# meteo-slave.net
KiCad netlist of a schematic drawn in EAGLE
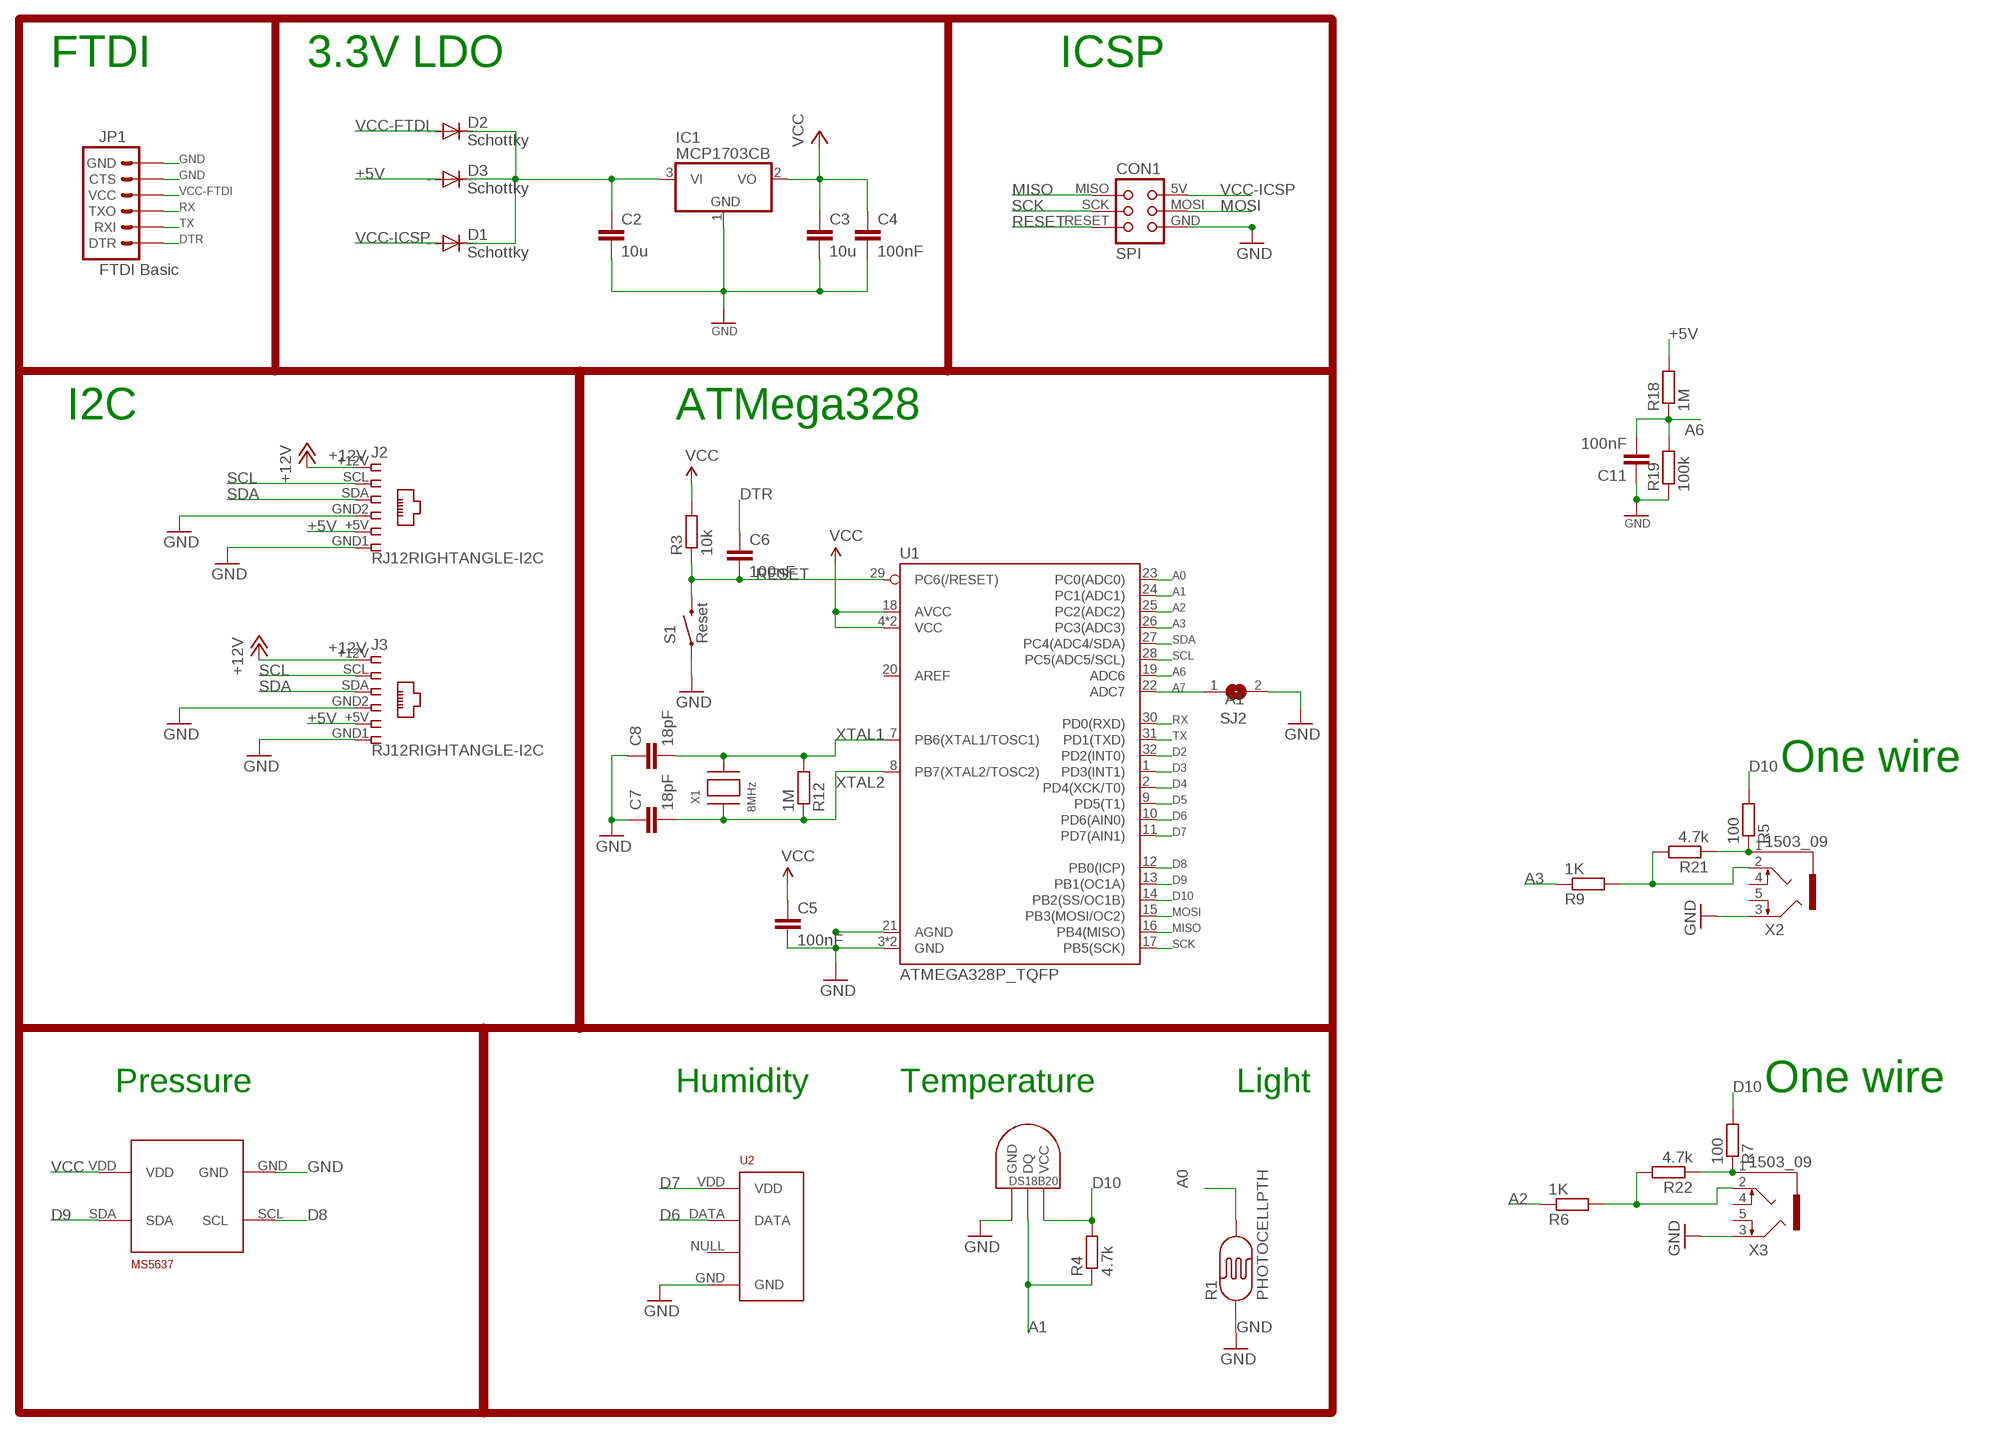
[diagram p0: schematic, sheet 1]

(export (version "E")
  (design (tool "Eeschema 10.0.6"))
  (components
    (comp (ref "C2")
      (value "10u")
      (footprint "eagle-import:C0805K")
      (fields (field (name "MPN") "77-VJ1206V106ZXQTBC"))
      (libsource (lib "eagle-import") (part "C-EUC0805K"))
    )
    (comp (ref "C3")
      (value "10u")
      (footprint "eagle-import:C0805K")
      (fields (field (name "MPN") "77-VJ1206V106ZXQTBC"))
      (libsource (lib "eagle-import") (part "C-EUC0805K"))
    )
    (comp (ref "C4")
      (value "100nF")
      (footprint "eagle-import:C0805K")
      (fields (field (name "MPN") "80-C1206C104K5R"))
      (libsource (lib "eagle-import") (part "C-EUC0805K"))
    )
    (comp (ref "C5")
      (value "100nF")
      (footprint "eagle-import:C0805K")
      (fields (field (name "MPN") "80-C1206C104K5R"))
      (libsource (lib "eagle-import") (part "C-EUC0805K"))
    )
    (comp (ref "C6")
      (value "100nF")
      (footprint "eagle-import:C0805K")
      (fields (field (name "MPN") "80-C1206C104K5R"))
      (libsource (lib "eagle-import") (part "C-EUC0805K"))
    )
    (comp (ref "C7")
      (value "18pF")
      (footprint "eagle-import:C0805K")
      (fields (field (name "MPN") "77-VJ1206A180JXXPBC"))
      (libsource (lib "eagle-import") (part "C-EUC0805K"))
    )
    (comp (ref "C8")
      (value "18pF")
      (footprint "eagle-import:C0805K")
      (fields (field (name "MPN") "77-VJ1206A180JXXPBC"))
      (libsource (lib "eagle-import") (part "C-EUC0805K"))
    )
    (comp (ref "C11")
      (value "100nF")
      (footprint "eagle-import:C0805K")
      (fields (field (name "MPN") "80-C1206C104K5R"))
      (libsource (lib "eagle-import") (part "C-EUC0805K"))
    )
    (comp (ref "CON1")
      (value "SPI")
      (footprint "eagle-import:TC2030-MCP")
      (libsource (lib "eagle-import") (part "TINYISPTAG"))
    )
    (comp (ref "D1")
      (value "Schottky")
      (footprint "eagle-import:SOD123")
      (fields (field (name "MPN") "621-1N5819HW-F"))
      (libsource (lib "eagle-import") (part "MBR0520LT"))
    )
    (comp (ref "D2")
      (value "Schottky")
      (footprint "eagle-import:SOD123")
      (fields (field (name "MPN") "621-1N5819HW-F"))
      (libsource (lib "eagle-import") (part "MBR0520LT"))
    )
    (comp (ref "D3")
      (value "Schottky")
      (footprint "eagle-import:SOD123")
      (fields (field (name "MPN") "621-1N5819HW-F"))
      (libsource (lib "eagle-import") (part "MBR0520LT"))
    )
    (comp (ref "IC1")
      (value "MCP1703CB")
      (footprint "eagle-import:SOT23")
      (libsource (lib "eagle-import") (part "MCP1703CB"))
    )
    (comp (ref "J2")
      (value "RJ12RIGHTANGLE-I2C")
      (footprint "eagle-import:RJ12-RIGHTANGLE-I2C")
      (libsource (lib "eagle-import") (part "RJ12RIGHTANGLE-I2C"))
    )
    (comp (ref "J3")
      (value "RJ12RIGHTANGLE-I2C")
      (footprint "eagle-import:RJ12-RIGHTANGLE-I2C")
      (libsource (lib "eagle-import") (part "RJ12RIGHTANGLE-I2C"))
    )
    (comp (ref "JP1")
      (value "FTDI Basic")
      (footprint "eagle-import:1X06")
      (libsource (lib "eagle-import") (part "ARDUINO_SERIAL_PROGRAMPTH"))
    )
    (comp (ref "R1")
      (value "PHOTOCELLPTH")
      (footprint "eagle-import:PHOTOCELL")
      (libsource (lib "eagle-import") (part "PHOTOCELLPTH"))
    )
    (comp (ref "R3")
      (value "10k")
      (footprint "eagle-import:R0805")
      (libsource (lib "eagle-import") (part "R-EU_R0805"))
    )
    (comp (ref "R4")
      (value "4.7k")
      (footprint "eagle-import:R0805")
      (libsource (lib "eagle-import") (part "resistor_348_R-EU_R0805"))
    )
    (comp (ref "R5")
      (value "100")
      (footprint "eagle-import:R0805")
      (libsource (lib "eagle-import") (part "R-EU_R0805"))
    )
    (comp (ref "R6")
      (value "1K")
      (footprint "eagle-import:R0805")
      (libsource (lib "eagle-import") (part "R-EU_R0805"))
    )
    (comp (ref "R7")
      (value "100")
      (footprint "eagle-import:R0805")
      (libsource (lib "eagle-import") (part "R-EU_R0805"))
    )
    (comp (ref "R9")
      (value "1K")
      (footprint "eagle-import:R0805")
      (libsource (lib "eagle-import") (part "R-EU_R0805"))
    )
    (comp (ref "R12")
      (value "1M")
      (footprint "eagle-import:R0805")
      (libsource (lib "eagle-import") (part "R-EU_R0805"))
    )
    (comp (ref "R18")
      (value "1M")
      (footprint "eagle-import:R0805")
      (libsource (lib "eagle-import") (part "R-EU_R0805"))
    )
    (comp (ref "R19")
      (value "100k")
      (footprint "eagle-import:R0805")
      (libsource (lib "eagle-import") (part "R-EU_R0805"))
    )
    (comp (ref "R21")
      (value "4.7k")
      (footprint "eagle-import:R0805")
      (libsource (lib "eagle-import") (part "resistor_R-EU_R0805"))
    )
    (comp (ref "R22")
      (value "4.7k")
      (footprint "eagle-import:R0805")
      (libsource (lib "eagle-import") (part "resistor_R-EU_R0805"))
    )
    (comp (ref "S1")
      (value "Reset")
      (footprint "eagle-import:TACTILE-SWITCH-SMD-ALT01")
      (libsource (lib "eagle-import") (part "SWITCH-MOMENTARY-2SMD-ALT01"))
    )
    (comp (ref "SJ2") (value "A1") (footprint "eagle-import:SJ") (libsource (lib "eagle-import") (part "SJ")))
    (comp (ref "U$1")
      (value "DS1820TO92")
      (footprint "eagle-import:DS1820")
      (libsource (lib "eagle-import") (part "DS1820TO92"))
    )
    (comp (ref "U$19")
      (value "MS5637WIDE")
      (footprint "eagle-import:MS5637WIDE")
      (libsource (lib "eagle-import") (part "MS5637WIDE"))
    )
    (comp (ref "U1")
      (value "ATMEGA328P_TQFP")
      (footprint "eagle-import:TQFP32-08")
      (libsource (lib "eagle-import") (part "ATMEGA328P_TQFP"))
    )
    (comp (ref "U2")
      (value "RHT03_DHT-22_AM2302")
      (footprint "eagle-import:RHT03_DHT-22")
      (libsource (lib "eagle-import") (part "RHT03_DHT-22_AM2302"))
    )
    (comp (ref "X1")
      (value "8MHz")
      (footprint "eagle-import:NX6035")
      (fields (field (name "MPN") "729-F60800010"))
      (libsource (lib "eagle-import") (part "XTALNX6035"))
    )
    (comp (ref "X2")
      (value "1503_09")
      (footprint "eagle-import:1503_09")
      (libsource (lib "eagle-import") (part "1503_09"))
    )
    (comp (ref "X3")
      (value "1503_09")
      (footprint "eagle-import:1503_09")
      (libsource (lib "eagle-import") (part "1503_09"))
    )
  )
  (nets
    (net (code "1") (name "+5V") (class "Default")
      (node (ref "D3") (pin "A") (pinfunction "A_A") (pintype "passive"))
      (node (ref "J2") (pin "+5V") (pinfunction "5_+5V") (pintype "bidirectional"))
      (node (ref "J3") (pin "+5V") (pinfunction "5_+5V") (pintype "bidirectional"))
      (node (ref "R18") (pin "2") (pinfunction "2_2") (pintype "passive"))
    )
    (net (code "2") (name "+12V") (class "Default")
      (node (ref "J2") (pin "+12V") (pinfunction "1_+12V") (pintype "bidirectional"))
      (node (ref "J3") (pin "+12V") (pinfunction "1_+12V") (pintype "bidirectional"))
    )
    (net (code "3") (name "A0") (class "Default")
      (node (ref "R1") (pin "2") (pinfunction "P$2_2") (pintype "bidirectional"))
      (node (ref "U1") (pin "23") (pinfunction "PC0(ADC0)_23") (pintype "bidirectional"))
    )
    (net (code "4") (name "A1") (class "Default")
      (node (ref "R4") (pin "1") (pinfunction "1_1") (pintype "passive"))
      (node (ref "U$1") (pin "DQ") (pinfunction "DQ_DQ") (pintype "bidirectional"))
      (node (ref "U1") (pin "24") (pinfunction "PC1(ADC1)_24") (pintype "bidirectional"))
    )
    (net (code "5") (name "A2") (class "Default")
      (node (ref "R6") (pin "1") (pinfunction "1_1") (pintype "passive"))
      (node (ref "U1") (pin "25") (pinfunction "PC2(ADC2)_25") (pintype "bidirectional"))
    )
    (net (code "6") (name "A3") (class "Default")
      (node (ref "R9") (pin "1") (pinfunction "1_1") (pintype "passive"))
      (node (ref "U1") (pin "26") (pinfunction "PC3(ADC3)_26") (pintype "bidirectional"))
    )
    (net (code "7") (name "A6") (class "Default")
      (node (ref "C11") (pin "2") (pinfunction "2_2") (pintype "passive"))
      (node (ref "R18") (pin "1") (pinfunction "1_1") (pintype "passive"))
      (node (ref "R19") (pin "2") (pinfunction "2_2") (pintype "passive"))
      (node (ref "U1") (pin "19") (pinfunction "ADC6_19") (pintype "bidirectional"))
    )
    (net (code "8") (name "A7") (class "Default")
      (node (ref "SJ2") (pin "1") (pinfunction "1_1") (pintype "passive"))
      (node (ref "U1") (pin "22") (pinfunction "ADC7_22") (pintype "bidirectional"))
    )
    (net (code "9") (name "D2") (class "Default")
      (node (ref "U1") (pin "32") (pinfunction "PD2(INT0)_32") (pintype "bidirectional"))
    )
    (net (code "10") (name "D3") (class "Default")
      (node (ref "U1") (pin "1") (pinfunction "PD3(INT1)_1") (pintype "bidirectional"))
    )
    (net (code "11") (name "D4") (class "Default")
      (node (ref "U1") (pin "2") (pinfunction "PD4(XCK/T0)_2") (pintype "bidirectional"))
    )
    (net (code "12") (name "D5") (class "Default")
      (node (ref "U1") (pin "9") (pinfunction "PD5(T1)_9") (pintype "bidirectional"))
    )
    (net (code "13") (name "D6") (class "Default")
      (node (ref "U1") (pin "10") (pinfunction "PD6(AIN0)_10") (pintype "bidirectional"))
      (node (ref "U2") (pin "DATA") (pinfunction "DATA_DATA") (pintype "bidirectional"))
    )
    (net (code "14") (name "D7") (class "Default")
      (node (ref "U1") (pin "11") (pinfunction "PD7(AIN1)_11") (pintype "bidirectional"))
      (node (ref "U2") (pin "VDD") (pinfunction "VDD_VDD") (pintype "power_in"))
    )
    (net (code "15") (name "D8") (class "Default")
      (node (ref "U$19") (pin "SCL") (pinfunction "SCL_SCL") (pintype "bidirectional"))
      (node (ref "U1") (pin "12") (pinfunction "PB0(ICP)_12") (pintype "bidirectional"))
    )
    (net (code "16") (name "D9") (class "Default")
      (node (ref "U$19") (pin "SDA") (pinfunction "SDA_SDA") (pintype "bidirectional"))
      (node (ref "U1") (pin "13") (pinfunction "PB1(OC1A)_13") (pintype "bidirectional"))
    )
    (net (code "17") (name "D10") (class "Default")
      (node (ref "R4") (pin "2") (pinfunction "2_2") (pintype "passive"))
      (node (ref "R5") (pin "2") (pinfunction "2_2") (pintype "passive"))
      (node (ref "R7") (pin "2") (pinfunction "2_2") (pintype "passive"))
      (node (ref "U$1") (pin "VDD") (pinfunction "VCC_VDD") (pintype "power_in"))
      (node (ref "U1") (pin "14") (pinfunction "PB2(SS/OC1B)_14") (pintype "bidirectional"))
    )
    (net (code "18") (name "DTR") (class "Default")
      (node (ref "C6") (pin "1") (pinfunction "1_1") (pintype "passive"))
      (node (ref "JP1") (pin "1") (pinfunction "DTR_1") (pintype "passive"))
    )
    (net (code "19") (name "GND") (class "Default")
      (node (ref "C11") (pin "1") (pinfunction "1_1") (pintype "passive"))
      (node (ref "C2") (pin "2") (pinfunction "2_2") (pintype "passive"))
      (node (ref "C3") (pin "2") (pinfunction "2_2") (pintype "passive"))
      (node (ref "C4") (pin "2") (pinfunction "2_2") (pintype "passive"))
      (node (ref "C5") (pin "2") (pinfunction "2_2") (pintype "passive"))
      (node (ref "C7") (pin "1") (pinfunction "1_1") (pintype "passive"))
      (node (ref "C8") (pin "1") (pinfunction "1_1") (pintype "passive"))
      (node (ref "CON1") (pin "GND") (pinfunction "GND_GND") (pintype "passive"))
      (node (ref "IC1") (pin "1") (pinfunction "GND_1") (pintype "passive"))
      (node (ref "J2") (pin "GND1") (pinfunction "6_GND1") (pintype "bidirectional"))
      (node (ref "J2") (pin "GND2") (pinfunction "4_GND2") (pintype "bidirectional"))
      (node (ref "J3") (pin "GND1") (pinfunction "6_GND1") (pintype "bidirectional"))
      (node (ref "J3") (pin "GND2") (pinfunction "4_GND2") (pintype "bidirectional"))
      (node (ref "JP1") (pin "5") (pinfunction "CTS_5") (pintype "passive"))
      (node (ref "JP1") (pin "6") (pinfunction "GND_6") (pintype "passive"))
      (node (ref "R1") (pin "1") (pinfunction "P$1_1") (pintype "bidirectional"))
      (node (ref "R19") (pin "1") (pinfunction "1_1") (pintype "passive"))
      (node (ref "S1") (pin "1") (pinfunction "1_1") (pintype "passive"))
      (node (ref "S1") (pin "2") (pinfunction "1_2") (pintype "passive"))
      (node (ref "SJ2") (pin "2") (pinfunction "2_2") (pintype "passive"))
      (node (ref "U$1") (pin "GND") (pinfunction "GND_GND") (pintype "power_in"))
      (node (ref "U$19") (pin "GND") (pinfunction "GND_GND") (pintype "bidirectional"))
      (node (ref "U1") (pin "21") (pinfunction "AGND_21") (pintype "bidirectional"))
      (node (ref "U1") (pin "3") (pinfunction "GND_3") (pintype "bidirectional"))
      (node (ref "U1") (pin "5") (pinfunction "GND_5") (pintype "bidirectional"))
      (node (ref "U2") (pin "GND") (pinfunction "GND_GND") (pintype "power_in"))
      (node (ref "X2") (pin "3") (pinfunction "3_3") (pintype "passive"))
      (node (ref "X3") (pin "3") (pinfunction "3_3") (pintype "passive"))
    )
    (net (code "20") (name "MISO") (class "Default")
      (node (ref "CON1") (pin "MISO") (pinfunction "MISO_MISO") (pintype "passive"))
      (node (ref "U1") (pin "16") (pinfunction "PB4(MISO)_16") (pintype "bidirectional"))
    )
    (net (code "21") (name "MOSI") (class "Default")
      (node (ref "CON1") (pin "MOSI") (pinfunction "MOSI_MOSI") (pintype "passive"))
      (node (ref "U1") (pin "15") (pinfunction "PB3(MOSI/OC2)_15") (pintype "bidirectional"))
    )
    (net (code "22") (name "Net-(IC1-VI)") (class "Default")
      (node (ref "C2") (pin "1") (pinfunction "1_1") (pintype "passive"))
      (node (ref "D1") (pin "C") (pinfunction "C_C") (pintype "passive"))
      (node (ref "D2") (pin "C") (pinfunction "C_C") (pintype "passive"))
      (node (ref "D3") (pin "C") (pinfunction "C_C") (pintype "passive"))
      (node (ref "IC1") (pin "3") (pinfunction "VI_3") (pintype "input"))
    )
    (net (code "23") (name "Net-(R21-Pad1)") (class "Default")
      (node (ref "R21") (pin "1") (pinfunction "1_1") (pintype "passive"))
      (node (ref "R5") (pin "1") (pinfunction "1_1") (pintype "passive"))
      (node (ref "X2") (pin "1") (pinfunction "1_1") (pintype "passive"))
    )
    (net (code "24") (name "Net-(R21-Pad2)") (class "Default")
      (node (ref "R21") (pin "2") (pinfunction "2_2") (pintype "passive"))
      (node (ref "R9") (pin "2") (pinfunction "2_2") (pintype "passive"))
      (node (ref "X2") (pin "2") (pinfunction "2_2") (pintype "passive"))
    )
    (net (code "25") (name "Net-(R22-Pad1)") (class "Default")
      (node (ref "R22") (pin "1") (pinfunction "1_1") (pintype "passive"))
      (node (ref "R7") (pin "1") (pinfunction "1_1") (pintype "passive"))
      (node (ref "X3") (pin "1") (pinfunction "1_1") (pintype "passive"))
    )
    (net (code "26") (name "Net-(R22-Pad2)") (class "Default")
      (node (ref "R22") (pin "2") (pinfunction "2_2") (pintype "passive"))
      (node (ref "R6") (pin "2") (pinfunction "2_2") (pintype "passive"))
      (node (ref "X3") (pin "2") (pinfunction "2_2") (pintype "passive"))
    )
    (net (code "27") (name "RESET") (class "Default")
      (node (ref "C6") (pin "2") (pinfunction "2_2") (pintype "passive"))
      (node (ref "CON1") (pin "RESET") (pinfunction "RESET_RESET") (pintype "passive"))
      (node (ref "R3") (pin "1") (pinfunction "1_1") (pintype "passive"))
      (node (ref "S1") (pin "3") (pinfunction "2_3") (pintype "passive"))
      (node (ref "S1") (pin "4") (pinfunction "2_4") (pintype "passive"))
      (node (ref "U1") (pin "29") (pinfunction "PC6(/RESET)_29") (pintype "bidirectional"))
    )
    (net (code "28") (name "RX") (class "Default")
      (node (ref "JP1") (pin "3") (pinfunction "TXO_3") (pintype "passive"))
      (node (ref "U1") (pin "30") (pinfunction "PD0(RXD)_30") (pintype "bidirectional"))
    )
    (net (code "29") (name "SCK") (class "Default")
      (node (ref "CON1") (pin "SCK") (pinfunction "SCK_SCK") (pintype "passive"))
      (node (ref "U1") (pin "17") (pinfunction "PB5(SCK)_17") (pintype "bidirectional"))
    )
    (net (code "30") (name "SCL") (class "Default")
      (node (ref "J2") (pin "SCL") (pinfunction "2_SCL") (pintype "bidirectional"))
      (node (ref "J3") (pin "SCL") (pinfunction "2_SCL") (pintype "bidirectional"))
      (node (ref "U1") (pin "28") (pinfunction "PC5(ADC5/SCL)_28") (pintype "bidirectional"))
    )
    (net (code "31") (name "SDA") (class "Default")
      (node (ref "J2") (pin "SDA") (pinfunction "3_SDA") (pintype "bidirectional"))
      (node (ref "J3") (pin "SDA") (pinfunction "3_SDA") (pintype "bidirectional"))
      (node (ref "U1") (pin "27") (pinfunction "PC4(ADC4/SDA)_27") (pintype "bidirectional"))
    )
    (net (code "32") (name "TX") (class "Default")
      (node (ref "JP1") (pin "2") (pinfunction "RXI_2") (pintype "passive"))
      (node (ref "U1") (pin "31") (pinfunction "PD1(TXD)_31") (pintype "bidirectional"))
    )
    (net (code "33") (name "VCC") (class "Default")
      (node (ref "C3") (pin "1") (pinfunction "1_1") (pintype "passive"))
      (node (ref "C4") (pin "1") (pinfunction "1_1") (pintype "passive"))
      (node (ref "C5") (pin "1") (pinfunction "1_1") (pintype "passive"))
      (node (ref "IC1") (pin "2") (pinfunction "VO_2") (pintype "passive"))
      (node (ref "R3") (pin "2") (pinfunction "2_2") (pintype "passive"))
      (node (ref "U$19") (pin "VDD") (pinfunction "VDD_VDD") (pintype "bidirectional"))
      (node (ref "U1") (pin "18") (pinfunction "AVCC_18") (pintype "bidirectional"))
      (node (ref "U1") (pin "4") (pinfunction "VCC_4") (pintype "bidirectional"))
      (node (ref "U1") (pin "6") (pinfunction "VCC_6") (pintype "bidirectional"))
    )
    (net (code "34") (name "VCC-FTDI") (class "Default")
      (node (ref "D2") (pin "A") (pinfunction "A_A") (pintype "passive"))
      (node (ref "JP1") (pin "4") (pinfunction "VCC_4") (pintype "passive"))
    )
    (net (code "35") (name "VCC-ICSP") (class "Default")
      (node (ref "CON1") (pin "5V") (pinfunction "VCC_5V") (pintype "passive"))
      (node (ref "D1") (pin "A") (pinfunction "A_A") (pintype "passive"))
    )
    (net (code "36") (name "XTAL1") (class "Default")
      (node (ref "C8") (pin "2") (pinfunction "2_2") (pintype "passive"))
      (node (ref "R12") (pin "2") (pinfunction "2_2") (pintype "passive"))
      (node (ref "U1") (pin "7") (pinfunction "PB6(XTAL1/TOSC1)_7") (pintype "bidirectional"))
      (node (ref "X1") (pin "P$2") (pinfunction "P$2_P$2") (pintype "bidirectional"))
    )
    (net (code "37") (name "XTAL2") (class "Default")
      (node (ref "C7") (pin "2") (pinfunction "2_2") (pintype "passive"))
      (node (ref "R12") (pin "1") (pinfunction "1_1") (pintype "passive"))
      (node (ref "U1") (pin "8") (pinfunction "PB7(XTAL2/TOSC2)_8") (pintype "bidirectional"))
      (node (ref "X1") (pin "P$1") (pinfunction "P$1_P$1") (pintype "bidirectional"))
    )
    (net (code "38") (name "unconnected-(U1-AREF-Pad20)") (class "Default")
      (node (ref "U1") (pin "20") (pinfunction "AREF_20") (pintype "bidirectional"))
    )
    (net (code "39") (name "unconnected-(U2-PadNULL)") (class "Default")
      (node (ref "U2") (pin "NULL") (pinfunction "NULL_NULL") (pintype "no_connect"))
    )
    (net (code "40") (name "unconnected-(X2-Pad4)") (class "Default")
      (node (ref "X2") (pin "4") (pinfunction "4_4") (pintype "passive"))
    )
    (net (code "41") (name "unconnected-(X2-Pad5)") (class "Default")
      (node (ref "X2") (pin "5") (pinfunction "5_5") (pintype "passive"))
    )
    (net (code "42") (name "unconnected-(X3-Pad4)") (class "Default")
      (node (ref "X3") (pin "4") (pinfunction "4_4") (pintype "passive"))
    )
    (net (code "43") (name "unconnected-(X3-Pad5)") (class "Default")
      (node (ref "X3") (pin "5") (pinfunction "5_5") (pintype "passive"))
    )
  )
)
